# M1713X.net
KiCad netlist of a schematic drawn in EAGLE
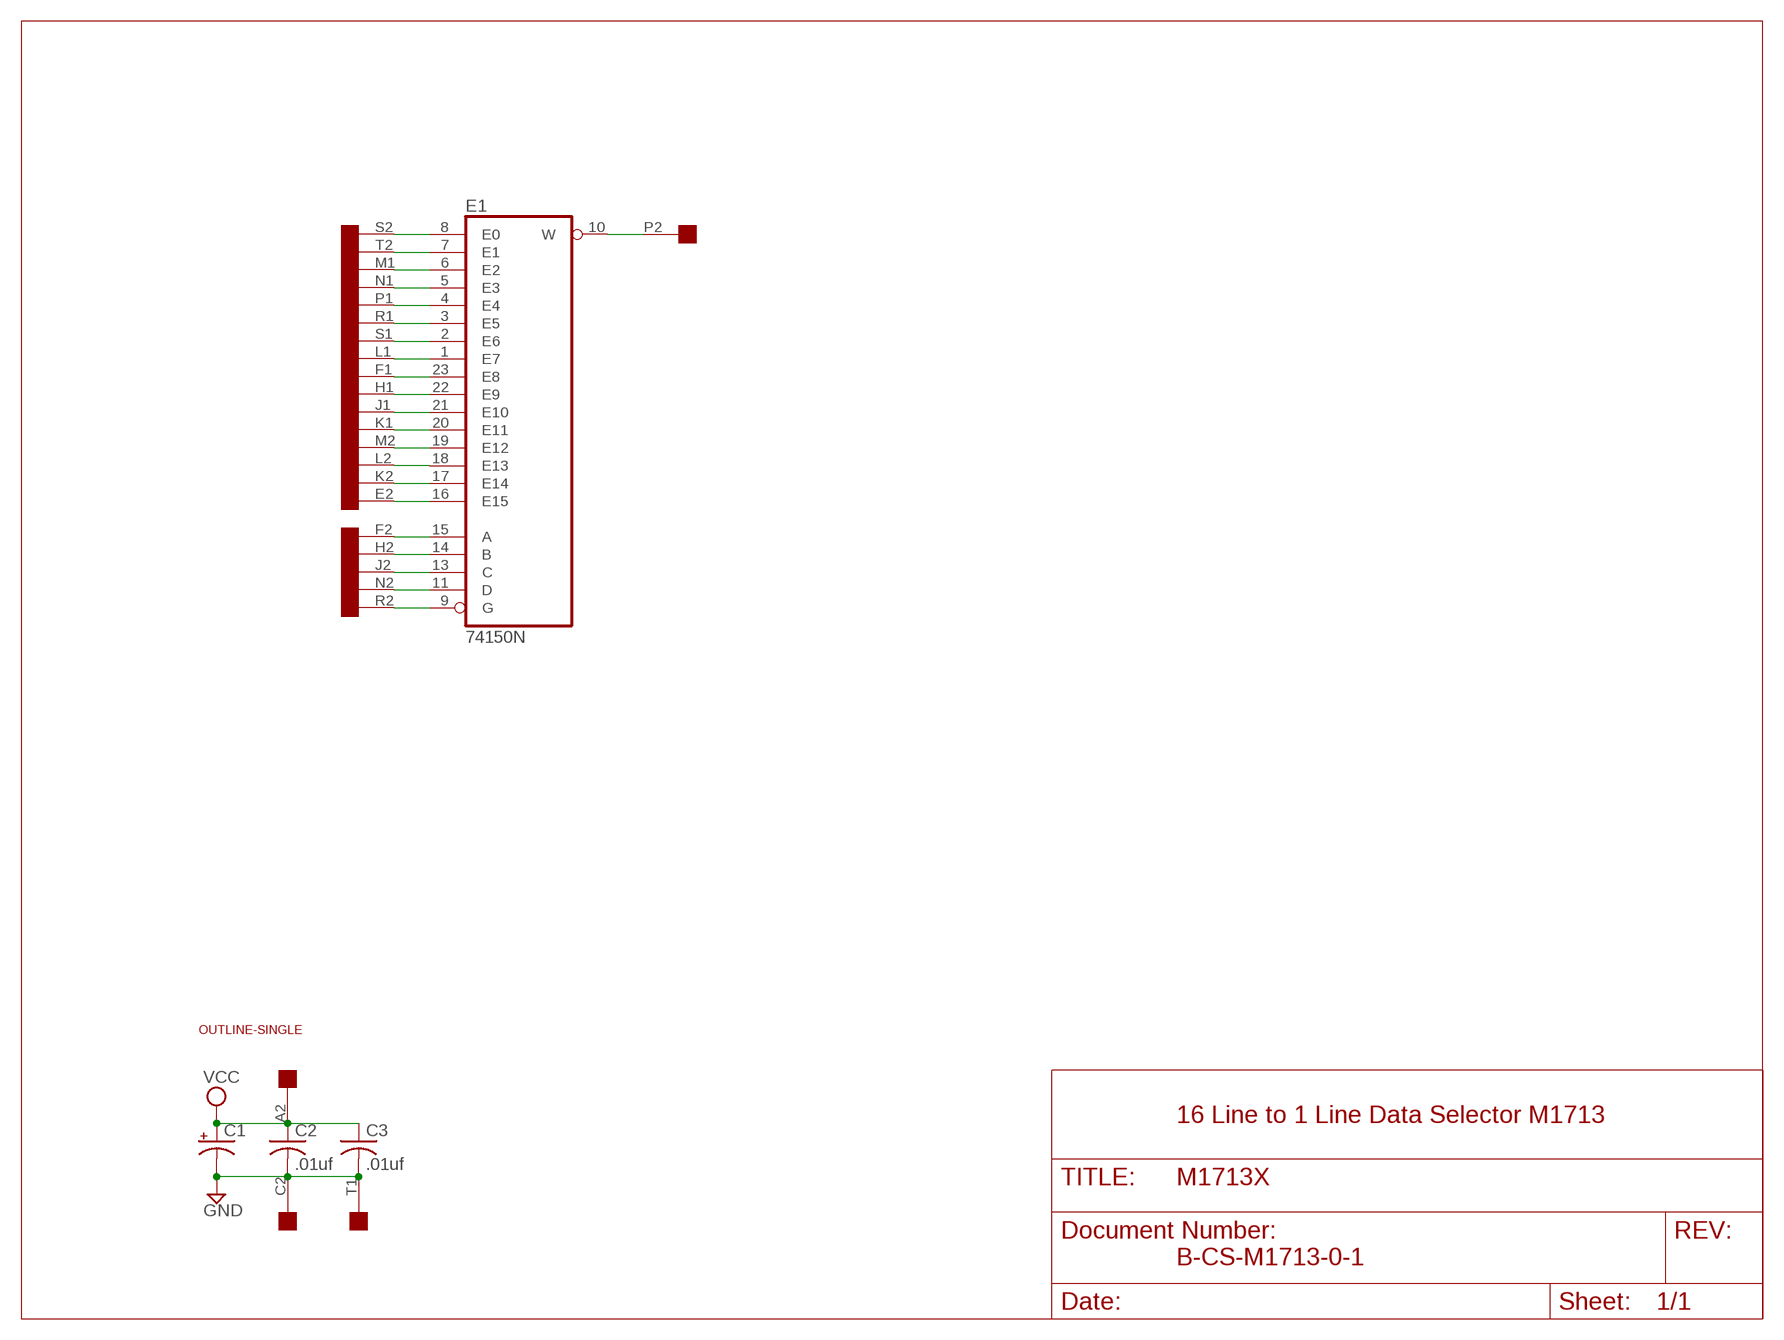
[diagram p0: schematic, sheet 1]

(export (version "E")
  (design (tool "Eeschema 10.0.6"))
  (components
    (comp (ref "C1")
      (value "CPOL-USE22-6AXIAL")
      (footprint "eagle-import:E22-6")
      (libsource (lib "eagle-import") (part "CPOL-USE22-6AXIAL"))
    )
    (comp (ref "C2")
      (value ".01uf")
      (footprint "eagle-import:C050-025X075")
      (libsource (lib "eagle-import") (part "C-US050-025X075"))
    )
    (comp (ref "C3")
      (value ".01uf")
      (footprint "eagle-import:C050-025X075")
      (libsource (lib "eagle-import") (part "C-US050-025X075"))
    )
    (comp (ref "E1")
      (value "74150N")
      (footprint "eagle-import:DIL24-6")
      (libsource (lib "eagle-import") (part "74150N"))
    )
    (comp (ref "U$1")
      (value "OUTLINE-SINGLE")
      (footprint "eagle-import:SINGLE")
      (libsource (lib "eagle-import") (part "OUTLINE-SINGLE"))
    )
    (comp (ref "U$2")
      (value "EDGE-2CONNECTOR")
      (footprint "eagle-import:EDGE-CON2")
      (libsource (lib "eagle-import") (part "EDGE-2CONNECTOR"))
    )
  )
  (nets
    (net (code "1") (name "GND") (class "Default")
      (node (ref "C1") (pin "-") (pinfunction "-_-") (pintype "passive"))
      (node (ref "C2") (pin "2") (pinfunction "2_2") (pintype "passive"))
      (node (ref "C3") (pin "2") (pinfunction "2_2") (pintype "passive"))
      (node (ref "U$2") (pin "C2") (pinfunction "1_C2") (pintype "bidirectional"))
      (node (ref "U$2") (pin "T1") (pinfunction "1_T1") (pintype "bidirectional"))
    )
    (net (code "2") (name "Net-(E1A-A)") (class "Default")
      (node (ref "E1") (pin "15") (pinfunction "A_15") (pintype "input"))
      (node (ref "U$2") (pin "F2") (pinfunction "1_F2") (pintype "bidirectional"))
    )
    (net (code "3") (name "Net-(E1A-B)") (class "Default")
      (node (ref "E1") (pin "14") (pinfunction "B_14") (pintype "input"))
      (node (ref "U$2") (pin "H2") (pinfunction "1_H2") (pintype "bidirectional"))
    )
    (net (code "4") (name "Net-(E1A-C)") (class "Default")
      (node (ref "E1") (pin "13") (pinfunction "C_13") (pintype "input"))
      (node (ref "U$2") (pin "J2") (pinfunction "1_J2") (pintype "bidirectional"))
    )
    (net (code "5") (name "Net-(E1A-D)") (class "Default")
      (node (ref "E1") (pin "11") (pinfunction "D_11") (pintype "input"))
      (node (ref "U$2") (pin "N2") (pinfunction "1_N2") (pintype "bidirectional"))
    )
    (net (code "6") (name "Net-(E1A-E0)") (class "Default")
      (node (ref "E1") (pin "8") (pinfunction "E0_8") (pintype "input"))
      (node (ref "U$2") (pin "S2") (pinfunction "1_S2") (pintype "bidirectional"))
    )
    (net (code "7") (name "Net-(E1A-E1)") (class "Default")
      (node (ref "E1") (pin "7") (pinfunction "E1_7") (pintype "input"))
      (node (ref "U$2") (pin "T2") (pinfunction "1_T2") (pintype "bidirectional"))
    )
    (net (code "8") (name "Net-(E1A-E2)") (class "Default")
      (node (ref "E1") (pin "6") (pinfunction "E2_6") (pintype "input"))
      (node (ref "U$2") (pin "M1") (pinfunction "1_M1") (pintype "bidirectional"))
    )
    (net (code "9") (name "Net-(E1A-E3)") (class "Default")
      (node (ref "E1") (pin "5") (pinfunction "E3_5") (pintype "input"))
      (node (ref "U$2") (pin "N1") (pinfunction "1_N1") (pintype "bidirectional"))
    )
    (net (code "10") (name "Net-(E1A-E4)") (class "Default")
      (node (ref "E1") (pin "4") (pinfunction "E4_4") (pintype "input"))
      (node (ref "U$2") (pin "P1") (pinfunction "1_P1") (pintype "bidirectional"))
    )
    (net (code "11") (name "Net-(E1A-E5)") (class "Default")
      (node (ref "E1") (pin "3") (pinfunction "E5_3") (pintype "input"))
      (node (ref "U$2") (pin "R1") (pinfunction "1_R1") (pintype "bidirectional"))
    )
    (net (code "12") (name "Net-(E1A-E6)") (class "Default")
      (node (ref "E1") (pin "2") (pinfunction "E6_2") (pintype "input"))
      (node (ref "U$2") (pin "S1") (pinfunction "1_S1") (pintype "bidirectional"))
    )
    (net (code "13") (name "Net-(E1A-E7)") (class "Default")
      (node (ref "E1") (pin "1") (pinfunction "E7_1") (pintype "input"))
      (node (ref "U$2") (pin "L1") (pinfunction "1_L1") (pintype "bidirectional"))
    )
    (net (code "14") (name "Net-(E1A-E8)") (class "Default")
      (node (ref "E1") (pin "23") (pinfunction "E8_23") (pintype "input"))
      (node (ref "U$2") (pin "F1") (pinfunction "1_F1") (pintype "bidirectional"))
    )
    (net (code "15") (name "Net-(E1A-E9)") (class "Default")
      (node (ref "E1") (pin "22") (pinfunction "E9_22") (pintype "input"))
      (node (ref "U$2") (pin "H1") (pinfunction "1_H1") (pintype "bidirectional"))
    )
    (net (code "16") (name "Net-(E1A-E10)") (class "Default")
      (node (ref "E1") (pin "21") (pinfunction "E10_21") (pintype "input"))
      (node (ref "U$2") (pin "J1") (pinfunction "1_J1") (pintype "bidirectional"))
    )
    (net (code "17") (name "Net-(E1A-E11)") (class "Default")
      (node (ref "E1") (pin "20") (pinfunction "E11_20") (pintype "input"))
      (node (ref "U$2") (pin "K1") (pinfunction "1_K1") (pintype "bidirectional"))
    )
    (net (code "18") (name "Net-(E1A-E12)") (class "Default")
      (node (ref "E1") (pin "19") (pinfunction "E12_19") (pintype "input"))
      (node (ref "U$2") (pin "M2") (pinfunction "1_M2") (pintype "bidirectional"))
    )
    (net (code "19") (name "Net-(E1A-E13)") (class "Default")
      (node (ref "E1") (pin "18") (pinfunction "E13_18") (pintype "input"))
      (node (ref "U$2") (pin "L2") (pinfunction "1_L2") (pintype "bidirectional"))
    )
    (net (code "20") (name "Net-(E1A-E14)") (class "Default")
      (node (ref "E1") (pin "17") (pinfunction "E14_17") (pintype "input"))
      (node (ref "U$2") (pin "K2") (pinfunction "1_K2") (pintype "bidirectional"))
    )
    (net (code "21") (name "Net-(E1A-E15)") (class "Default")
      (node (ref "E1") (pin "16") (pinfunction "E15_16") (pintype "input"))
      (node (ref "U$2") (pin "E2") (pinfunction "1_E2") (pintype "bidirectional"))
    )
    (net (code "22") (name "Net-(E1A-G)") (class "Default")
      (node (ref "E1") (pin "9") (pinfunction "G_9") (pintype "input"))
      (node (ref "U$2") (pin "R2") (pinfunction "1_R2") (pintype "bidirectional"))
    )
    (net (code "23") (name "Net-(E1A-W)") (class "Default")
      (node (ref "E1") (pin "10") (pinfunction "W_10") (pintype "output"))
      (node (ref "U$2") (pin "P2") (pinfunction "1_P2") (pintype "bidirectional"))
    )
    (net (code "24") (name "VCC") (class "Default")
      (node (ref "C1") (pin "+") (pinfunction "+_+") (pintype "passive"))
      (node (ref "C2") (pin "1") (pinfunction "1_1") (pintype "passive"))
      (node (ref "C3") (pin "1") (pinfunction "1_1") (pintype "passive"))
      (node (ref "U$2") (pin "A2") (pinfunction "1_A2") (pintype "bidirectional"))
    )
  )
)
